# P08R60.net
KiCad netlist of a schematic drawn in EAGLE
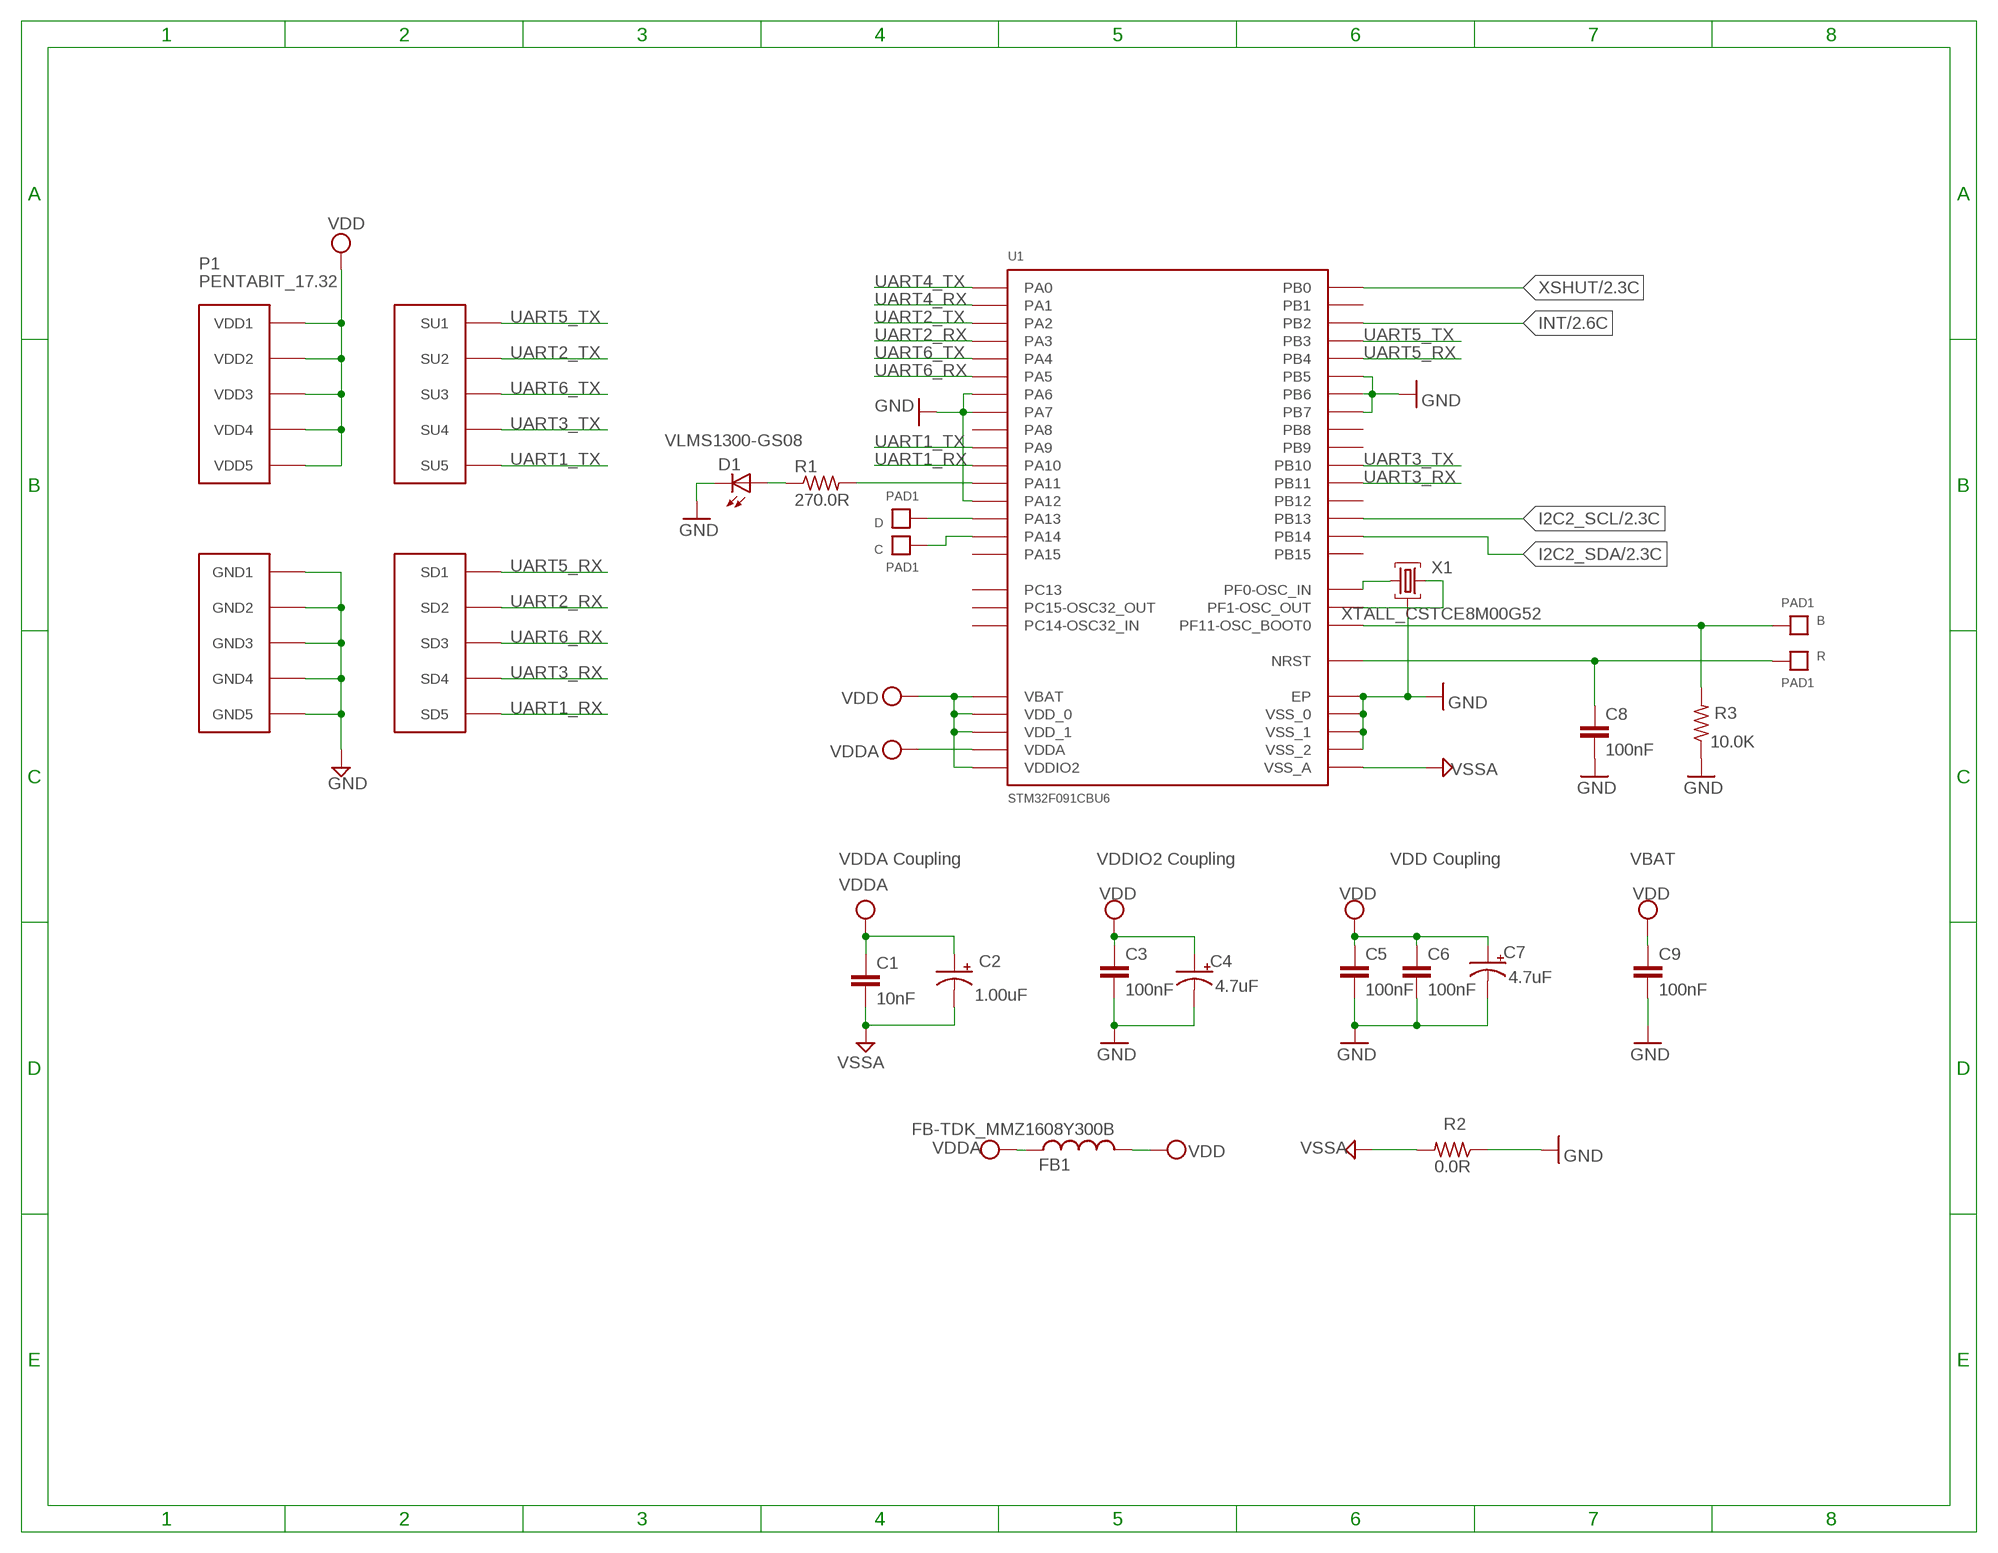
[diagram p0: schematic, sheet 1]
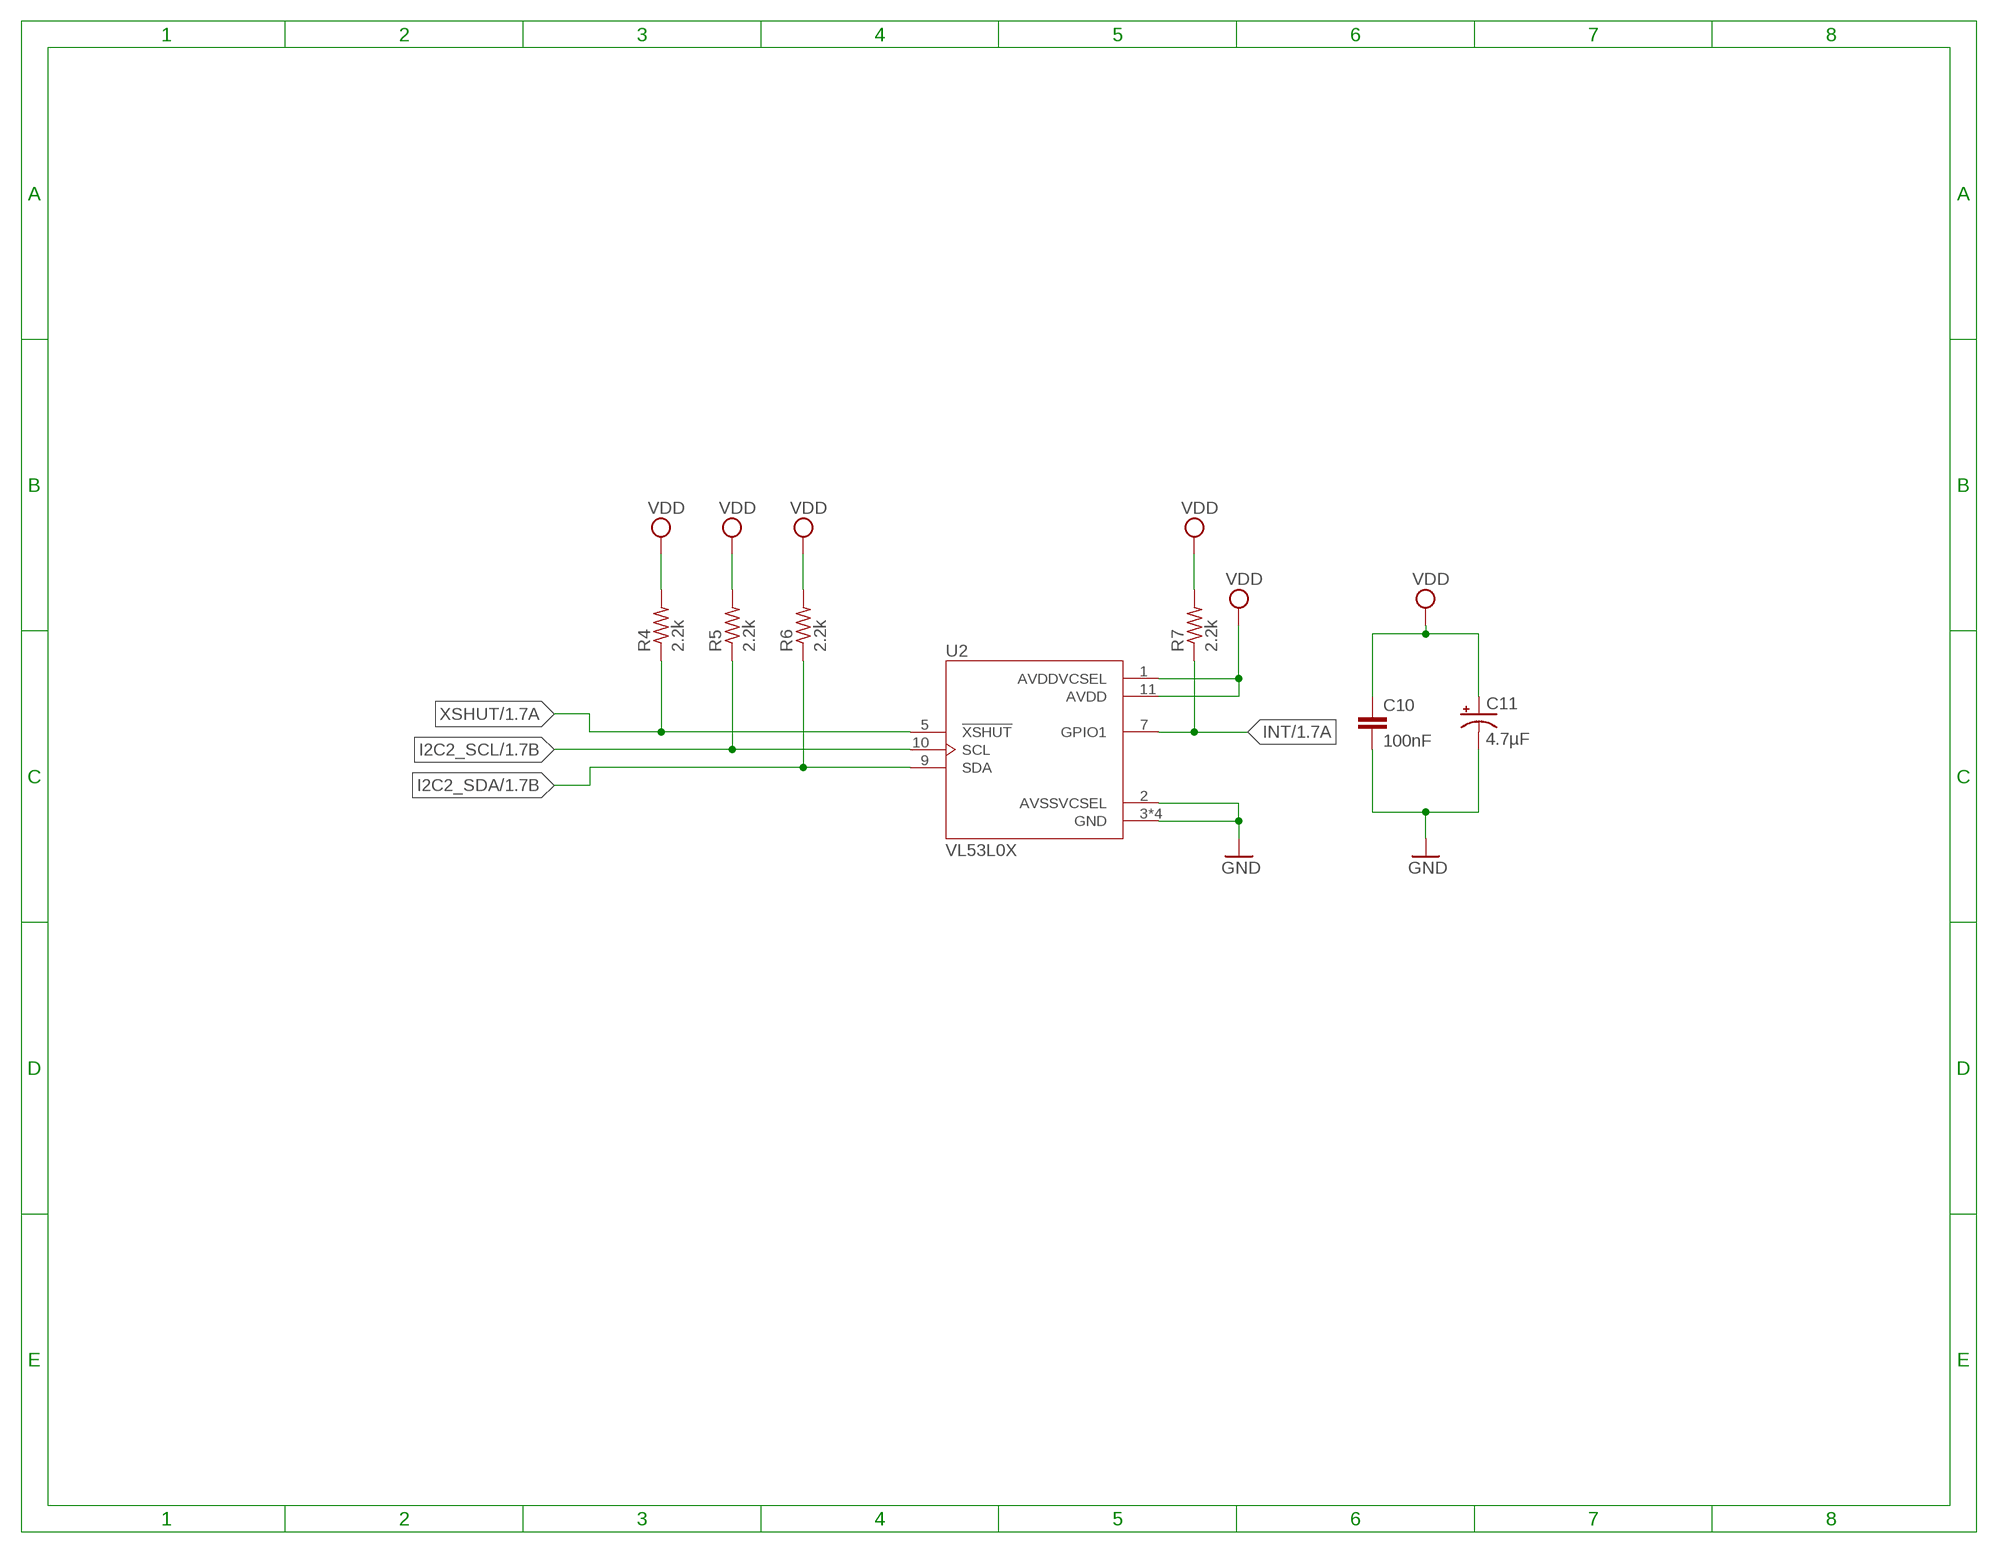
[diagram p1: schematic, sheet 2]

(export (version "E")
  (design (tool "Eeschema 10.0.6"))
  (components
    (comp (ref "C10")
      (value "100nF")
      (footprint "eagle-import:C-0603")
      (fields
        (field (name "MFN") "KEMET")
        (field (name "MPN") "C0603C104K8RACTU")
        (field (name "OCTOPART_URL") "https://octopart.com/0603yc104k4t2a-avx+interconnect+%2F+elco-8120651")
        (field (name "TOLERANCE") "±10%")
        (field (name "VOLTAGE_RATING") "16.0 V")
      )
      (libsource (lib "eagle-import") (part "C-0603"))
    )
    (comp (ref "C11")
      (value "4.7uF")
      (footprint "eagle-import:C-0805")
      (fields
        (field (name "CAPACITANCE") "4.7µF")
        (field (name "MFN") "Murata")
        (field (name "MPN") "GRM21BC81E475KA12L")
        (field (name "OCTOPART_URL") "https://octopart.com/grm21bc81e475ka12l-murata-10331911?r=sp&s=RY3qZSD8T6mG6TC9CHI5qQ")
        (field (name "TOLERANCE") "10%")
        (field (name "VOLTAGE_RATING") "25V")
      )
      (libsource (lib "eagle-import") (part "C-0805"))
    )
    (comp (ref "R4")
      (value "2.2k")
      (footprint "eagle-import:R-0603")
      (fields
        (field (name "MFN") "Yageo")
        (field (name "MPN") "RC0603FR-07270RL")
        (field (name "OCTOPART_URL") "https://octopart.com/crcw06032k20fkea-vishay-40018987")
        (field (name "TOLERANCE") "±1%")
      )
      (libsource (lib "eagle-import") (part "R-0603"))
    )
    (comp (ref "R5")
      (value "2.2k")
      (footprint "eagle-import:R-0603")
      (fields
        (field (name "MFN") "Yageo")
        (field (name "MPN") "RC0603FR-07270RL")
        (field (name "OCTOPART_URL") "https://octopart.com/crcw06032k20fkea-vishay-40018987")
        (field (name "TOLERANCE") "±1%")
      )
      (libsource (lib "eagle-import") (part "R-0603"))
    )
    (comp (ref "R6")
      (value "2.2k")
      (footprint "eagle-import:R-0603")
      (fields
        (field (name "MFN") "Yageo")
        (field (name "MPN") "RC0603FR-07270RL")
        (field (name "OCTOPART_URL") "https://octopart.com/crcw06032k20fkea-vishay-40018987")
        (field (name "TOLERANCE") "±1%")
      )
      (libsource (lib "eagle-import") (part "R-0603"))
    )
    (comp (ref "R7")
      (value "2.2k")
      (footprint "eagle-import:R-0603")
      (fields
        (field (name "MFN") "Yageo")
        (field (name "MPN") "RC0603FR-07270RL")
        (field (name "OCTOPART_URL") "https://octopart.com/crcw06032k20fkea-vishay-40018987")
        (field (name "TOLERANCE") "±1%")
      )
      (libsource (lib "eagle-import") (part "R-0603"))
    )
    (comp (ref "U2")
      (value "VL53L0X")
      (footprint "eagle-import:SENSOR_VL53L0X")
      (fields (field (name "MPN") "VL53L0CXV0DH/1"))
      (libsource (lib "eagle-import") (part "VL53L0X"))
    )
    (comp (ref "B")
      (value "PAD1")
      (footprint "eagle-import:PAD1")
      (libsource (lib "eagle-import") (part "PAD1"))
    )
    (comp (ref "C")
      (value "PAD1")
      (footprint "eagle-import:PAD1")
      (libsource (lib "eagle-import") (part "PAD1"))
    )
    (comp (ref "C1")
      (value "10nF")
      (footprint "eagle-import:C-0603")
      (fields
        (field (name "CAPACITANCE") "10nF")
        (field (name "MFN") "KEMET")
        (field (name "MPN") "C0603C103K5RACTU")
        (field (name "OCTOPART_URL") "https://octopart.com/c0603c103k5ractu-kemet-133094?r=sp&s=R_iPBxLnSmGqhkU2rIMFpg")
        (field (name "TOLERANCE") "10%")
        (field (name "VOLTAGE_RATING") "50V")
      )
      (libsource (lib "eagle-import") (part "C-0603"))
    )
    (comp (ref "C2")
      (value "1.00uF")
      (footprint "eagle-import:C-0805-POL")
      (fields
        (field (name "CAPACITANCE") "1.00uF")
        (field (name "MFN") "Yageo")
        (field (name "MPN") "CC0805KKX7R7BB105")
        (field (name "OCTOPART_URL") "https://octopart.com/cc0805kkx7r7bb105-yageo-8376555?r=sp&s=YKl1wwtkROau_X5nniH2ig")
        (field (name "TOLERANCE") "10%")
        (field (name "VOLTAGE_RATING") "16V")
      )
      (libsource (lib "eagle-import") (part "C-0805-POL"))
    )
    (comp (ref "C3")
      (value "100nF")
      (footprint "eagle-import:C-0603")
      (fields
        (field (name "CAPACITANCE") "100nF")
        (field (name "MFN") "KEMET")
        (field (name "MPN") "C0603C104K8RACTU")
        (field (name "OCTOPART_URL") "https://octopart.com/c0603c104k8ractu-kemet-145075?r=sp&s=9bS9ASSwSEqMCE9KBEQZ0g")
        (field (name "TOLERANCE") "10%")
        (field (name "VOLTAGE_RATING") "10V")
      )
      (libsource (lib "eagle-import") (part "C-0603"))
    )
    (comp (ref "C4")
      (value "4.7uF")
      (footprint "eagle-import:C-0805-POL")
      (fields
        (field (name "CAPACITANCE") "4.7uF")
        (field (name "MFN") "Murata")
        (field (name "MPN") "GRM21BC81E475KA12L")
        (field (name "OCTOPART_URL") "https://octopart.com/grm21bc81e475ka12l-murata-10331911?r=sp&s=RY3qZSD8T6mG6TC9CHI5qQ")
        (field (name "TOLERANCE") "10%")
        (field (name "VOLTAGE_RATING") "25V")
      )
      (libsource (lib "eagle-import") (part "C-0805-POL"))
    )
    (comp (ref "C5")
      (value "100nF")
      (footprint "eagle-import:C-0603")
      (fields
        (field (name "CAPACITANCE") "100nF")
        (field (name "MFN") "KEMET")
        (field (name "MPN") "C0603C104K8RACTU")
        (field (name "OCTOPART_URL") "https://octopart.com/c0603c104k8ractu-kemet-145075?r=sp&s=9bS9ASSwSEqMCE9KBEQZ0g")
        (field (name "TOLERANCE") "10%")
        (field (name "VOLTAGE_RATING") "10")
      )
      (libsource (lib "eagle-import") (part "C-0603"))
    )
    (comp (ref "C6")
      (value "100nF")
      (footprint "eagle-import:C-0603")
      (fields
        (field (name "CAPACITANCE") "100nF")
        (field (name "MFN") "KEMET")
        (field (name "MPN") "C0603C104K8RACTU")
        (field (name "OCTOPART_URL") "https://octopart.com/c0603c104k8ractu-kemet-145075?r=sp&s=9bS9ASSwSEqMCE9KBEQZ0g")
        (field (name "TOLERANCE") "10%")
        (field (name "VOLTAGE_RATING") "10V")
      )
      (libsource (lib "eagle-import") (part "C-0603"))
    )
    (comp (ref "C7")
      (value "4.7uF")
      (footprint "eagle-import:C-0805-POL")
      (fields
        (field (name "CAPACITANCE") "4.7uF")
        (field (name "MFN") "Murata")
        (field (name "MPN") "GRM21BC81E475KA12L")
        (field (name "OCTOPART_URL") "https://octopart.com/grm21bc81e475ka12l-murata-10331911?r=sp&s=RY3qZSD8T6mG6TC9CHI5qQ")
        (field (name "TOLERANCE") "10%")
        (field (name "VOLTAGE_RATING") "25V")
      )
      (libsource (lib "eagle-import") (part "C-0805-POL"))
    )
    (comp (ref "C8")
      (value "100nF")
      (footprint "eagle-import:C-0603")
      (fields
        (field (name "CAPACITANCE") "100nF")
        (field (name "MFN") "KEMET")
        (field (name "MPN") "C0603C104K8RACTU")
        (field (name "OCTOPART_URL") "https://octopart.com/c0603c104k8ractu-kemet-145075?r=sp&s=9bS9ASSwSEqMCE9KBEQZ0g")
        (field (name "TOLERANCE") "10%")
        (field (name "VOLTAGE_RATING") "10V")
      )
      (libsource (lib "eagle-import") (part "C-0603"))
    )
    (comp (ref "C9")
      (value "100nF")
      (footprint "eagle-import:C-0603")
      (fields
        (field (name "CAPACITANCE") "100nF")
        (field (name "MFN") "KEMET")
        (field (name "MPN") "C0603C104K8RACTU")
        (field (name "OCTOPART_URL") "https://octopart.com/c0603c104k8ractu-kemet-145075?r=sp&s=9bS9ASSwSEqMCE9KBEQZ0g")
        (field (name "TOLERANCE") "10V")
        (field (name "VOLTAGE_RATING") "10%")
      )
      (libsource (lib "eagle-import") (part "C-0603"))
    )
    (comp (ref "D")
      (value "PAD1")
      (footprint "eagle-import:PAD1")
      (libsource (lib "eagle-import") (part "PAD1"))
    )
    (comp (ref "D1")
      (value "VLMS1300-GS08")
      (footprint "eagle-import:VLMS1300-GS08")
      (fields
        (field (name "MFN") "Vishay")
        (field (name "MPN") "VLMS1300-GS08")
        (field (name "OCTOPART_URL") "https://octopart.com/vlms1300-gs08-vishay-21709201?r=sp&s=_gcP4_q8T1SC6PJQPTQ9yA")
      )
      (libsource (lib "eagle-import") (part "VLMS1300-GS08"))
    )
    (comp (ref "FB1")
      (value "FB-TDK_MMZ1608Y300B")
      (footprint "eagle-import:FB-TDK_MMZ1608Y300B")
      (fields
        (field (name "MFN") "TDK ")
        (field (name "MPN") "MMZ1608Y300B")
        (field (name "OCTOPART_URL") "https://octopart.com/mmz1608y300b-tdk-368280?r=sp&s=cd9_2ZEqQ9q9UNBuQgHAiA")
      )
      (libsource (lib "eagle-import") (part "FB-TDK_MMZ1608Y300B"))
    )
    (comp (ref "P1")
      (value "PENTABIT_17.32")
      (footprint "eagle-import:PENTABIT_17.32")
      (libsource (lib "eagle-import") (part "PENTABIT_?17.32"))
    )
    (comp (ref "R")
      (value "PAD1")
      (footprint "eagle-import:PAD1")
      (libsource (lib "eagle-import") (part "PAD1"))
    )
    (comp (ref "R1")
      (value "270.0R")
      (footprint "eagle-import:R-0603")
      (fields
        (field (name "MFN") "Yageo")
        (field (name "MPN") "RC0603FR-07270RL")
        (field (name "OCTOPART_URL") "https://octopart.com/search?q=RC0603FR-07270RL&start=0")
        (field (name "RESISTANCE") "270.0 Ohm")
        (field (name "TOLERANCE") "1%")
      )
      (libsource (lib "eagle-import") (part "R-0603"))
    )
    (comp (ref "R2")
      (value "0.0R")
      (footprint "eagle-import:R-0603")
      (fields
        (field (name "MFN") "Yageo")
        (field (name "MPN") "RC0603JR-070RL")
        (field (name "OCTOPART_URL") "https://octopart.com/rc0603jr-070rl-yageo-1241539?r=sp&s=X2NteqRjRNWrnx42Y0aliA")
        (field (name "RESISTANCE") "0.0 Ohm")
      )
      (libsource (lib "eagle-import") (part "R-0603"))
    )
    (comp (ref "R3")
      (value "10.0K")
      (footprint "eagle-import:R-0603")
      (fields
        (field (name "MFN") "Yageo")
        (field (name "MPN") "RC0603JR-0710KL")
        (field (name "OCTOPART_URL") "https://octopart.com/search?q=RC0603JR-0710KL&start=0")
        (field (name "RESISTANCE") "10.0K Ohm")
        (field (name "TOLERANCE") "5%")
      )
      (libsource (lib "eagle-import") (part "R-0603"))
    )
    (comp (ref "U1")
      (value "STM32F091CBU6")
      (footprint "eagle-import:STM32F091CBU6")
      (libsource (lib "eagle-import") (part "STM32F091CBU6"))
    )
    (comp (ref "X1")
      (value "XTALL_CSTCE8M00G52")
      (footprint "eagle-import:XTALL_CSTCE8M00G52")
      (fields (field (name "MPN") "CSTCE8M00G52Z-R0"))
      (libsource (lib "eagle-import") (part "XTALL_CSTCE8M00G52"))
    )
  )
  (nets
    (net (code "1") (name "GND") (class "Default")
      (node (ref "C10") (pin "2") (pinfunction "2_2") (pintype "passive"))
      (node (ref "C11") (pin "2") (pinfunction "-_2") (pintype "passive"))
      (node (ref "C3") (pin "2") (pinfunction "2_2") (pintype "passive"))
      (node (ref "C4") (pin "2") (pinfunction "-_2") (pintype "passive"))
      (node (ref "C5") (pin "2") (pinfunction "2_2") (pintype "passive"))
      (node (ref "C6") (pin "2") (pinfunction "2_2") (pintype "passive"))
      (node (ref "C7") (pin "2") (pinfunction "-_2") (pintype "passive"))
      (node (ref "C8") (pin "2") (pinfunction "2_2") (pintype "passive"))
      (node (ref "C9") (pin "2") (pinfunction "2_2") (pintype "passive"))
      (node (ref "D1") (pin "C") (pinfunction "C_C") (pintype "passive"))
      (node (ref "P1") (pin "PAD_PD10") (pinfunction "GND5_PAD_PD10") (pintype "power_in"))
      (node (ref "P1") (pin "PAD_PD6") (pinfunction "GND1_PAD_PD6") (pintype "power_in"))
      (node (ref "P1") (pin "PAD_PD7") (pinfunction "GND2_PAD_PD7") (pintype "power_in"))
      (node (ref "P1") (pin "PAD_PD8") (pinfunction "GND3_PAD_PD8") (pintype "power_in"))
      (node (ref "P1") (pin "PAD_PD9") (pinfunction "GND4_PAD_PD9") (pintype "power_in"))
      (node (ref "R2") (pin "1") (pinfunction "1_1") (pintype "passive"))
      (node (ref "R3") (pin "1") (pinfunction "1_1") (pintype "passive"))
      (node (ref "U1") (pin "EP") (pinfunction "EP_EP") (pintype "power_in"))
      (node (ref "U1") (pin "P$16") (pinfunction "PA6_P$16") (pintype "bidirectional"))
      (node (ref "U1") (pin "P$17") (pinfunction "PA7_P$17") (pintype "bidirectional"))
      (node (ref "U1") (pin "P$23") (pinfunction "VSS_0_P$23") (pintype "power_in"))
      (node (ref "U1") (pin "P$33") (pinfunction "PA12_P$33") (pintype "bidirectional"))
      (node (ref "U1") (pin "P$35") (pinfunction "VSS_1_P$35") (pintype "power_in"))
      (node (ref "U1") (pin "P$41") (pinfunction "PB5_P$41") (pintype "bidirectional"))
      (node (ref "U1") (pin "P$42") (pinfunction "PB6_P$42") (pintype "bidirectional"))
      (node (ref "U1") (pin "P$43") (pinfunction "PB7_P$43") (pintype "bidirectional"))
      (node (ref "U1") (pin "P$47") (pinfunction "VSS_2_P$47") (pintype "power_in"))
      (node (ref "U2") (pin "12") (pinfunction "GND_12") (pintype "power_in"))
      (node (ref "U2") (pin "2") (pinfunction "AVSSVCSEL_2") (pintype "power_in"))
      (node (ref "U2") (pin "3") (pinfunction "GND_3") (pintype "power_in"))
      (node (ref "U2") (pin "4") (pinfunction "GND_4") (pintype "power_in"))
      (node (ref "U2") (pin "6") (pinfunction "GND_6") (pintype "power_in"))
      (node (ref "X1") (pin "P$2") (pinfunction "2_P$2") (pintype "passive"))
    )
    (net (code "2") (name "I2C2_SCL") (class "Default")
      (node (ref "R5") (pin "1") (pinfunction "1_1") (pintype "passive"))
      (node (ref "U1") (pin "P$26") (pinfunction "PB13_P$26") (pintype "bidirectional"))
      (node (ref "U2") (pin "10") (pinfunction "SCL_10") (pintype "input"))
    )
    (net (code "3") (name "I2C2_SDA") (class "Default")
      (node (ref "R6") (pin "1") (pinfunction "1_1") (pintype "passive"))
      (node (ref "U1") (pin "P$27") (pinfunction "PB14_P$27") (pintype "bidirectional"))
      (node (ref "U2") (pin "9") (pinfunction "SDA_9") (pintype "bidirectional"))
    )
    (net (code "4") (name "INT") (class "Default")
      (node (ref "R7") (pin "1") (pinfunction "1_1") (pintype "passive"))
      (node (ref "U1") (pin "P$20") (pinfunction "PB2_P$20") (pintype "bidirectional"))
      (node (ref "U2") (pin "7") (pinfunction "GPIO1_7") (pintype "output"))
    )
    (net (code "5") (name "Net-(D1-PadA)") (class "Default")
      (node (ref "D1") (pin "A") (pinfunction "A_A") (pintype "passive"))
      (node (ref "R1") (pin "1") (pinfunction "1_1") (pintype "passive"))
    )
    (net (code "6") (name "Net-(U1-NRST)") (class "Default")
      (node (ref "C8") (pin "1") (pinfunction "1_1") (pintype "passive"))
      (node (ref "R") (pin "P$1") (pinfunction "P$1_P$1") (pintype "passive"))
      (node (ref "R") (pin "P$2") (pinfunction "P$1_P$2") (pintype "passive"))
      (node (ref "U1") (pin "P$7") (pinfunction "NRST_P$7") (pintype "passive"))
    )
    (net (code "7") (name "Net-(U1-PA11)") (class "Default")
      (node (ref "R1") (pin "2") (pinfunction "2_2") (pintype "passive"))
      (node (ref "U1") (pin "P$32") (pinfunction "PA11_P$32") (pintype "bidirectional"))
    )
    (net (code "8") (name "Net-(U1-PA13)") (class "Default")
      (node (ref "D") (pin "P$1") (pinfunction "P$1_P$1") (pintype "passive"))
      (node (ref "D") (pin "P$2") (pinfunction "P$1_P$2") (pintype "passive"))
      (node (ref "U1") (pin "P$34") (pinfunction "PA13_P$34") (pintype "bidirectional"))
    )
    (net (code "9") (name "Net-(U1-PA14)") (class "Default")
      (node (ref "C") (pin "P$1") (pinfunction "P$1_P$1") (pintype "passive"))
      (node (ref "C") (pin "P$2") (pinfunction "P$1_P$2") (pintype "passive"))
      (node (ref "U1") (pin "P$37") (pinfunction "PA14_P$37") (pintype "bidirectional"))
    )
    (net (code "10") (name "Net-(U1-PF0-OSC_IN)") (class "Default")
      (node (ref "U1") (pin "P$5") (pinfunction "PF0-OSC_IN_P$5") (pintype "bidirectional"))
      (node (ref "X1") (pin "P$1") (pinfunction "1_P$1") (pintype "passive"))
    )
    (net (code "11") (name "Net-(U1-PF1-OSC_OUT)") (class "Default")
      (node (ref "U1") (pin "P$6") (pinfunction "PF1-OSC_OUT_P$6") (pintype "bidirectional"))
      (node (ref "X1") (pin "P$3") (pinfunction "3_P$3") (pintype "passive"))
    )
    (net (code "12") (name "Net-(U1-PF11-OSC_BOOT0)") (class "Default")
      (node (ref "B") (pin "P$1") (pinfunction "P$1_P$1") (pintype "passive"))
      (node (ref "B") (pin "P$2") (pinfunction "P$1_P$2") (pintype "passive"))
      (node (ref "R3") (pin "2") (pinfunction "2_2") (pintype "passive"))
      (node (ref "U1") (pin "P$44") (pinfunction "PF11-OSC_BOOT0_P$44") (pintype "bidirectional"))
    )
    (net (code "13") (name "UART1_RX") (class "Default")
      (node (ref "P1") (pin "PAD_PD5") (pinfunction "SD5_PAD_PD5") (pintype "bidirectional"))
      (node (ref "U1") (pin "P$31") (pinfunction "PA10_P$31") (pintype "bidirectional"))
    )
    (net (code "14") (name "UART1_TX") (class "Default")
      (node (ref "P1") (pin "PAD_PU5") (pinfunction "SU5_PAD_PU5") (pintype "bidirectional"))
      (node (ref "U1") (pin "P$30") (pinfunction "PA9_P$30") (pintype "bidirectional"))
    )
    (net (code "15") (name "UART2_RX") (class "Default")
      (node (ref "P1") (pin "PAD_PD2") (pinfunction "SD2_PAD_PD2") (pintype "bidirectional"))
      (node (ref "U1") (pin "P$13") (pinfunction "PA3_P$13") (pintype "bidirectional"))
    )
    (net (code "16") (name "UART2_TX") (class "Default")
      (node (ref "P1") (pin "PAD_PU2") (pinfunction "SU2_PAD_PU2") (pintype "bidirectional"))
      (node (ref "U1") (pin "P$12") (pinfunction "PA2_P$12") (pintype "bidirectional"))
    )
    (net (code "17") (name "UART3_RX") (class "Default")
      (node (ref "P1") (pin "PAD_PD4") (pinfunction "SD4_PAD_PD4") (pintype "bidirectional"))
      (node (ref "U1") (pin "P$22") (pinfunction "PB11_P$22") (pintype "bidirectional"))
    )
    (net (code "18") (name "UART3_TX") (class "Default")
      (node (ref "P1") (pin "PAD_PU4") (pinfunction "SU4_PAD_PU4") (pintype "bidirectional"))
      (node (ref "U1") (pin "P$21") (pinfunction "PB10_P$21") (pintype "bidirectional"))
    )
    (net (code "19") (name "UART4_RX") (class "Default")
      (node (ref "U1") (pin "P$11") (pinfunction "PA1_P$11") (pintype "bidirectional"))
    )
    (net (code "20") (name "UART4_TX") (class "Default")
      (node (ref "U1") (pin "P$10") (pinfunction "PA0_P$10") (pintype "bidirectional"))
    )
    (net (code "21") (name "UART5_RX") (class "Default")
      (node (ref "P1") (pin "PAD_PD1") (pinfunction "SD1_PAD_PD1") (pintype "bidirectional"))
      (node (ref "U1") (pin "P$40") (pinfunction "PB4_P$40") (pintype "bidirectional"))
    )
    (net (code "22") (name "UART5_TX") (class "Default")
      (node (ref "P1") (pin "PAD_PU1") (pinfunction "SU1_PAD_PU1") (pintype "bidirectional"))
      (node (ref "U1") (pin "P$39") (pinfunction "PB3_P$39") (pintype "bidirectional"))
    )
    (net (code "23") (name "UART6_RX") (class "Default")
      (node (ref "P1") (pin "PAD_PD3") (pinfunction "SD3_PAD_PD3") (pintype "bidirectional"))
      (node (ref "U1") (pin "P$15") (pinfunction "PA5_P$15") (pintype "bidirectional"))
    )
    (net (code "24") (name "UART6_TX") (class "Default")
      (node (ref "P1") (pin "PAD_PU3") (pinfunction "SU3_PAD_PU3") (pintype "bidirectional"))
      (node (ref "U1") (pin "P$14") (pinfunction "PA4_P$14") (pintype "bidirectional"))
    )
    (net (code "25") (name "VDD") (class "Default")
      (node (ref "C10") (pin "1") (pinfunction "1_1") (pintype "passive"))
      (node (ref "C11") (pin "1") (pinfunction "+_1") (pintype "passive"))
      (node (ref "C3") (pin "1") (pinfunction "1_1") (pintype "passive"))
      (node (ref "C4") (pin "1") (pinfunction "+_1") (pintype "passive"))
      (node (ref "C5") (pin "1") (pinfunction "1_1") (pintype "passive"))
      (node (ref "C6") (pin "1") (pinfunction "1_1") (pintype "passive"))
      (node (ref "C7") (pin "1") (pinfunction "+_1") (pintype "passive"))
      (node (ref "C9") (pin "1") (pinfunction "1_1") (pintype "passive"))
      (node (ref "FB1") (pin "2") (pinfunction "2_2") (pintype "passive"))
      (node (ref "P1") (pin "PAD_PU10") (pinfunction "VDD5_PAD_PU10") (pintype "power_in"))
      (node (ref "P1") (pin "PAD_PU6") (pinfunction "VDD1_PAD_PU6") (pintype "power_in"))
      (node (ref "P1") (pin "PAD_PU7") (pinfunction "VDD2_PAD_PU7") (pintype "power_in"))
      (node (ref "P1") (pin "PAD_PU8") (pinfunction "VDD3_PAD_PU8") (pintype "power_in"))
      (node (ref "P1") (pin "PAD_PU9") (pinfunction "VDD4_PAD_PU9") (pintype "power_in"))
      (node (ref "R4") (pin "2") (pinfunction "2_2") (pintype "passive"))
      (node (ref "R5") (pin "2") (pinfunction "2_2") (pintype "passive"))
      (node (ref "R6") (pin "2") (pinfunction "2_2") (pintype "passive"))
      (node (ref "R7") (pin "2") (pinfunction "2_2") (pintype "passive"))
      (node (ref "U1") (pin "P$1") (pinfunction "VBAT_P$1") (pintype "power_in"))
      (node (ref "U1") (pin "P$24") (pinfunction "VDD_0_P$24") (pintype "power_in"))
      (node (ref "U1") (pin "P$36") (pinfunction "VDDIO2_P$36") (pintype "power_in"))
      (node (ref "U1") (pin "P$48") (pinfunction "VDD_1_P$48") (pintype "power_in"))
      (node (ref "U2") (pin "1") (pinfunction "AVDDVCSEL_1") (pintype "power_in"))
      (node (ref "U2") (pin "11") (pinfunction "AVDD_11") (pintype "power_in"))
    )
    (net (code "26") (name "VDDA") (class "Default")
      (node (ref "C1") (pin "1") (pinfunction "1_1") (pintype "passive"))
      (node (ref "C2") (pin "1") (pinfunction "+_1") (pintype "passive"))
      (node (ref "FB1") (pin "1") (pinfunction "1_1") (pintype "passive"))
      (node (ref "U1") (pin "P$9") (pinfunction "VDDA_P$9") (pintype "power_in"))
    )
    (net (code "27") (name "VSSA") (class "Default")
      (node (ref "C1") (pin "2") (pinfunction "2_2") (pintype "passive"))
      (node (ref "C2") (pin "2") (pinfunction "-_2") (pintype "passive"))
      (node (ref "R2") (pin "2") (pinfunction "2_2") (pintype "passive"))
      (node (ref "U1") (pin "P$8") (pinfunction "VSS_A_P$8") (pintype "power_in"))
    )
    (net (code "28") (name "XSHUT") (class "Default")
      (node (ref "R4") (pin "1") (pinfunction "1_1") (pintype "passive"))
      (node (ref "U1") (pin "P$18") (pinfunction "PB0_P$18") (pintype "bidirectional"))
      (node (ref "U2") (pin "5") (pinfunction "~{XSHUT}_5") (pintype "input"))
    )
    (net (code "29") (name "unconnected-(U1-PA8-PadP$29)") (class "Default")
      (node (ref "U1") (pin "P$29") (pinfunction "PA8_P$29") (pintype "bidirectional"))
    )
    (net (code "30") (name "unconnected-(U1-PA15-PadP$38)") (class "Default")
      (node (ref "U1") (pin "P$38") (pinfunction "PA15_P$38") (pintype "bidirectional"))
    )
    (net (code "31") (name "unconnected-(U1-PB1-PadP$19)") (class "Default")
      (node (ref "U1") (pin "P$19") (pinfunction "PB1_P$19") (pintype "bidirectional"))
    )
    (net (code "32") (name "unconnected-(U1-PB8-PadP$45)") (class "Default")
      (node (ref "U1") (pin "P$45") (pinfunction "PB8_P$45") (pintype "bidirectional"))
    )
    (net (code "33") (name "unconnected-(U1-PB9-PadP$46)") (class "Default")
      (node (ref "U1") (pin "P$46") (pinfunction "PB9_P$46") (pintype "bidirectional"))
    )
    (net (code "34") (name "unconnected-(U1-PB12-PadP$25)") (class "Default")
      (node (ref "U1") (pin "P$25") (pinfunction "PB12_P$25") (pintype "bidirectional"))
    )
    (net (code "35") (name "unconnected-(U1-PB15-PadP$28)") (class "Default")
      (node (ref "U1") (pin "P$28") (pinfunction "PB15_P$28") (pintype "bidirectional"))
    )
    (net (code "36") (name "unconnected-(U1-PC13-PadP$2)") (class "Default")
      (node (ref "U1") (pin "P$2") (pinfunction "PC13_P$2") (pintype "bidirectional"))
    )
    (net (code "37") (name "unconnected-(U1-PC14-OSC32_IN-PadP$3)") (class "Default")
      (node (ref "U1") (pin "P$3") (pinfunction "PC14-OSC32_IN_P$3") (pintype "bidirectional"))
    )
    (net (code "38") (name "unconnected-(U1-PC15-OSC32_OUT-PadP$4)") (class "Default")
      (node (ref "U1") (pin "P$4") (pinfunction "PC15-OSC32_OUT_P$4") (pintype "bidirectional"))
    )
  )
)
